# PG4_SHEET2.net
KiCad netlist of a schematic drawn in Altium Designer
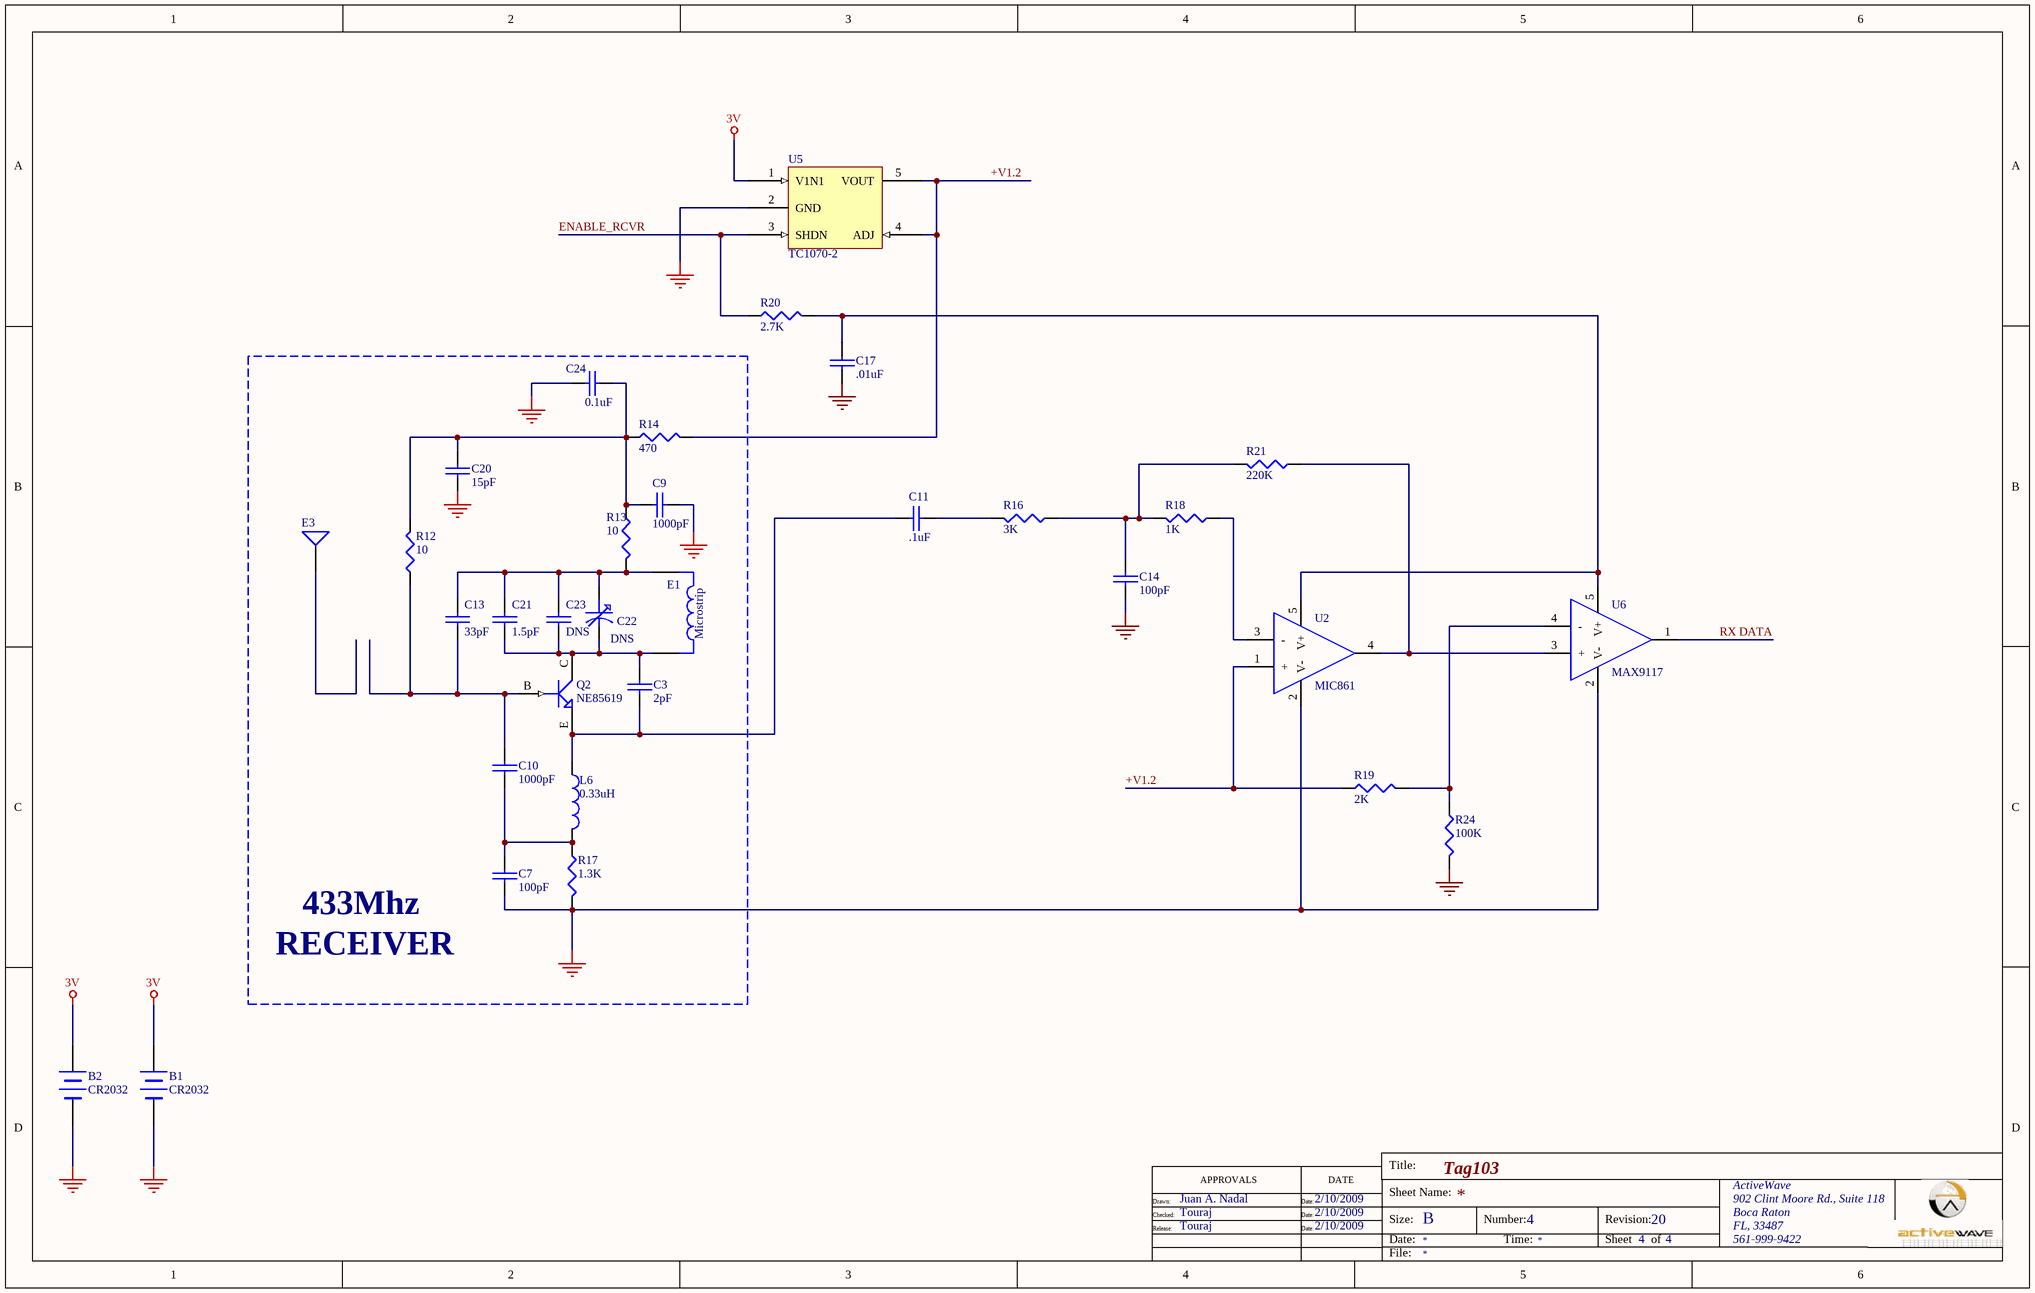
[diagram p0: PG4 SHEET2.schdoc]

(export (version "E")
  (design (tool "Eeschema 10.0.6"))
  (components
    (comp (ref "B1")
      (value "CR2032")
      (footprint "BATT HOLDER1")
      (description "Battery")
      (fields (field (name "Comment") "BATT HOLDER COIN CR2032 CUT"))
      (libsource (lib "ActiveWave MasterLib") (part "BATTERY2"))
    )
    (comp (ref "B2")
      (value "CR2032")
      (footprint "BATT HOLDER COIN CR2032 CUT_VER1")
      (description "Battery")
      (fields (field (name "Comment") "BATT HOLDER COIN CR2032 CUT"))
      (libsource (lib "ActiveWave MasterLib") (part "BATTERY2"))
    )
    (comp (ref "C3")
      (value "2pF")
      (footprint "0603")
      (description "Capacitor")
      (fields (field (name "Comment") "2 pF"))
      (libsource (lib "ActiveWave MasterLib") (part "CAP-0603"))
    )
    (comp (ref "C7")
      (value "100pF")
      (footprint "0603")
      (description "Capacitor")
      (fields (field (name "Comment") "100 pF"))
      (libsource (lib "ActiveWave MasterLib") (part "CAP-0603"))
    )
    (comp (ref "C9")
      (value "1000pF")
      (footprint "0603")
      (description "Capacitor")
      (fields (field (name "Comment") "1000 pF"))
      (libsource (lib "ActiveWave MasterLib") (part "CAP-0603"))
    )
    (comp (ref "C10")
      (value "1000pF")
      (footprint "0603")
      (description "Capacitor")
      (fields (field (name "Comment") "1000 pF"))
      (libsource (lib "ActiveWave MasterLib") (part "CAP-0603"))
    )
    (comp (ref "C11")
      (value ".1uF")
      (footprint "0603")
      (description "Capacitor")
      (libsource (lib "ActiveWave MasterLib") (part "CAP-0603"))
    )
    (comp (ref "C13")
      (value "33pF")
      (footprint "0603")
      (description "Capacitor")
      (fields (field (name "Comment") "33 pF"))
      (libsource (lib "ActiveWave MasterLib") (part "CAP-0603"))
    )
    (comp (ref "C14")
      (value "100pF")
      (footprint "0603")
      (description "Capacitor")
      (libsource (lib "ActiveWave MasterLib") (part "CAP-0603"))
    )
    (comp (ref "C17")
      (value ".01uF")
      (footprint "0603")
      (description "Capacitor")
      (libsource (lib "ActiveWave MasterLib") (part "CAP-0603"))
    )
    (comp (ref "C20")
      (value "15pF")
      (footprint "0603")
      (description "Capacitor")
      (libsource (lib "ActiveWave MasterLib") (part "CAP-0603"))
    )
    (comp (ref "C21")
      (value "1.5pF")
      (footprint "0603")
      (description "Capacitor")
      (libsource (lib "ActiveWave MasterLib") (part "CAP-0603"))
    )
    (comp (ref "C22") (value "DNS") (footprint "0603") (libsource (lib "*") (part "CAPACITOR VAR")))
    (comp (ref "C23")
      (value "DNS")
      (footprint "0603")
      (description "Capacitor")
      (libsource (lib "ActiveWave MasterLib") (part "CAP-0603"))
    )
    (comp (ref "C24")
      (value "0.1uF")
      (footprint "0603")
      (description "Capacitor")
      (fields (field (name "Comment") "0.1 uF"))
      (libsource (lib "ActiveWave MasterLib") (part "CAP-0603"))
    )
    (comp (ref "E1")
      (value "Microstrip")
      (footprint "Antenna")
      (fields (field (name "ITEM-DESCRIPTION") "Microstrip"))
      (libsource (lib "ActiveWave MasterLib") (part "ANTENNA"))
    )
    (comp (ref "E3")
      (value "*")
      (footprint "Antenna1")
      (libsource (lib "ActiveWave MasterLib") (part "Antenna1"))
    )
    (comp (ref "L6")
      (value "0.33uH")
      (footprint "0603")
      (libsource (lib "ActiveWave MasterLib") (part "INDUCTOR"))
    )
    (comp (ref "Q2")
      (value "NE85619")
      (footprint "3 PIN ULTRA SUPER MINI MOLD")
      (description "NPN Transistor")
      (libsource (lib "ActiveWave MasterLib") (part "NE85619"))
    )
    (comp (ref "R12")
      (value "10")
      (footprint "0603")
      (libsource (lib "ActiveWave MasterLib") (part "RES-0603"))
    )
    (comp (ref "R13")
      (value "10")
      (footprint "0603")
      (libsource (lib "ActiveWave MasterLib") (part "RES-0603"))
    )
    (comp (ref "R14")
      (value "470")
      (footprint "0603")
      (libsource (lib "ActiveWave MasterLib") (part "RES-0603"))
    )
    (comp (ref "R16")
      (value "3K")
      (footprint "0603")
      (fields (field (name "Comment") "22K"))
      (libsource (lib "ActiveWave MasterLib") (part "RES-0603"))
    )
    (comp (ref "R17")
      (value "1.3K")
      (footprint "0603")
      (fields (field (name "Comment") "2K"))
      (libsource (lib "ActiveWave MasterLib") (part "RES-0603"))
    )
    (comp (ref "R18")
      (value "1K")
      (footprint "0603")
      (libsource (lib "ActiveWave MasterLib") (part "RES-0603"))
    )
    (comp (ref "R19")
      (value "2K")
      (footprint "0603")
      (libsource (lib "ActiveWave MasterLib") (part "RES-0603"))
    )
    (comp (ref "R20")
      (value "2.7K")
      (footprint "0603")
      (libsource (lib "ActiveWave MasterLib") (part "RES-0603"))
    )
    (comp (ref "R21")
      (value "220K")
      (footprint "0603")
      (libsource (lib "ActiveWave MasterLib") (part "RES-0603"))
    )
    (comp (ref "R24")
      (value "100K")
      (footprint "0603")
      (libsource (lib "ActiveWave MasterLib") (part "RES-0603"))
    )
    (comp (ref "U2")
      (value "MIC861")
      (footprint "SC70")
      (libsource (lib "ActiveWave MasterLib") (part "OPAMP MIC861"))
    )
    (comp (ref "U5")
      (value "TC1070-2")
      (footprint "SOT23-5A")
      (fields (field (name "Comment") "TC1070"))
      (libsource (lib "ActiveWave MasterLib") (part "TC1070-2"))
    )
    (comp (ref "U6")
      (value "MAX9117")
      (footprint "SC70")
      (fields (field (name "Comment") "MAX9119EXK+"))
      (libsource (lib "ActiveWave MasterLib") (part "COMPARATOR MAX9117"))
    )
  )
  (nets
    (net (code "1") (name "/+V1.2") (class "Default")
      (node (ref "R14") (pin "2") (pinfunction "2_2") (pintype "passive"))
      (node (ref "R19") (pin "1") (pinfunction "1_1") (pintype "passive"))
      (node (ref "U2") (pin "1") (pinfunction "+_1") (pintype "passive"))
      (node (ref "U5") (pin "4") (pinfunction "ADJ_4") (pintype "input"))
      (node (ref "U5") (pin "5") (pinfunction "VOUT_5") (pintype "power_in"))
    )
    (net (code "2") (name "/ENABLE_RCVR") (class "Default")
      (node (ref "R20") (pin "1") (pinfunction "1_1") (pintype "passive"))
      (node (ref "U5") (pin "3") (pinfunction "SHDN_3") (pintype "input"))
    )
    (net (code "3") (name "/RX DATA") (class "Default")
      (node (ref "U6") (pin "1") (pinfunction "OUT_1") (pintype "passive"))
    )
    (net (code "4") (name "3V") (class "Default")
      (node (ref "B1") (pin "2") (pinfunction "+_2") (pintype "passive"))
      (node (ref "B2") (pin "2") (pinfunction "+_2") (pintype "passive"))
      (node (ref "U5") (pin "1") (pinfunction "V1N1_1") (pintype "input"))
    )
    (net (code "5") (name "GND") (class "Default")
      (node (ref "B1") (pin "1") (pinfunction "-_1") (pintype "passive"))
      (node (ref "B2") (pin "1") (pinfunction "-_1") (pintype "passive"))
      (node (ref "C14") (pin "1") (pinfunction "1_1") (pintype "passive"))
      (node (ref "C17") (pin "2") (pinfunction "2_2") (pintype "passive"))
      (node (ref "C20") (pin "2") (pinfunction "2_2") (pintype "passive"))
      (node (ref "C24") (pin "2") (pinfunction "2_2") (pintype "passive"))
      (node (ref "C7") (pin "2") (pinfunction "2_2") (pintype "passive"))
      (node (ref "C9") (pin "2") (pinfunction "2_2") (pintype "passive"))
      (node (ref "R17") (pin "2") (pinfunction "2_2") (pintype "passive"))
      (node (ref "R24") (pin "2") (pinfunction "2_2") (pintype "passive"))
      (node (ref "U2") (pin "2") (pinfunction "V-_2") (pintype "passive"))
      (node (ref "U5") (pin "2") (pinfunction "GND_2") (pintype "power_in"))
      (node (ref "U6") (pin "2") (pinfunction "V-_2") (pintype "passive"))
    )
    (net (code "6") (name "Net-(C10-Pad1)") (class "Default")
      (node (ref "C10") (pin "1") (pinfunction "1_1") (pintype "passive"))
      (node (ref "C13") (pin "2") (pinfunction "2_2") (pintype "passive"))
      (node (ref "Q2") (pin "B") (pinfunction "B_B") (pintype "input"))
      (node (ref "R12") (pin "1") (pinfunction "1_1") (pintype "passive"))
    )
    (net (code "7") (name "Net-(C10-Pad2)") (class "Default")
      (node (ref "C10") (pin "2") (pinfunction "2_2") (pintype "passive"))
      (node (ref "C7") (pin "1") (pinfunction "1_1") (pintype "passive"))
      (node (ref "L6") (pin "2") (pinfunction "2_2") (pintype "passive"))
      (node (ref "R17") (pin "1") (pinfunction "1_1") (pintype "passive"))
    )
    (net (code "8") (name "Net-(C11-Pad1)") (class "Default")
      (node (ref "C11") (pin "1") (pinfunction "1_1") (pintype "passive"))
      (node (ref "C3") (pin "2") (pinfunction "2_2") (pintype "passive"))
      (node (ref "L6") (pin "1") (pinfunction "1_1") (pintype "passive"))
      (node (ref "Q2") (pin "E") (pinfunction "E_E") (pintype "passive"))
    )
    (net (code "9") (name "Net-(C11-Pad2)") (class "Default")
      (node (ref "C11") (pin "2") (pinfunction "2_2") (pintype "passive"))
      (node (ref "R16") (pin "2") (pinfunction "2_2") (pintype "passive"))
    )
    (net (code "10") (name "Net-(C13-Pad1)") (class "Default")
      (node (ref "C13") (pin "1") (pinfunction "1_1") (pintype "passive"))
      (node (ref "C21") (pin "1") (pinfunction "1_1") (pintype "passive"))
      (node (ref "C22") (pin "1") (pinfunction "1_1") (pintype "passive"))
      (node (ref "C23") (pin "1") (pinfunction "1_1") (pintype "passive"))
      (node (ref "E1") (pin "1") (pinfunction "1_1") (pintype "passive"))
      (node (ref "R13") (pin "2") (pinfunction "2_2") (pintype "passive"))
    )
    (net (code "11") (name "Net-(C14-Pad2)") (class "Default")
      (node (ref "C14") (pin "2") (pinfunction "2_2") (pintype "passive"))
      (node (ref "R16") (pin "1") (pinfunction "1_1") (pintype "passive"))
      (node (ref "R18") (pin "2") (pinfunction "2_2") (pintype "passive"))
      (node (ref "R21") (pin "2") (pinfunction "2_2") (pintype "passive"))
    )
    (net (code "12") (name "Net-(C20-Pad1)") (class "Default")
      (node (ref "C20") (pin "1") (pinfunction "1_1") (pintype "passive"))
      (node (ref "C24") (pin "1") (pinfunction "1_1") (pintype "passive"))
      (node (ref "C9") (pin "1") (pinfunction "1_1") (pintype "passive"))
      (node (ref "R12") (pin "2") (pinfunction "2_2") (pintype "passive"))
      (node (ref "R13") (pin "1") (pinfunction "1_1") (pintype "passive"))
      (node (ref "R14") (pin "1") (pinfunction "1_1") (pintype "passive"))
    )
    (net (code "13") (name "Net-(C21-Pad2)") (class "Default")
      (node (ref "C21") (pin "2") (pinfunction "2_2") (pintype "passive"))
      (node (ref "C22") (pin "2") (pinfunction "2_2") (pintype "passive"))
      (node (ref "C23") (pin "2") (pinfunction "2_2") (pintype "passive"))
      (node (ref "C3") (pin "1") (pinfunction "1_1") (pintype "passive"))
      (node (ref "E1") (pin "2") (pinfunction "2_2") (pintype "passive"))
      (node (ref "Q2") (pin "C") (pinfunction "C_C") (pintype "passive"))
    )
    (net (code "14") (name "Net-(U2--)") (class "Default")
      (node (ref "R18") (pin "1") (pinfunction "1_1") (pintype "passive"))
      (node (ref "U2") (pin "3") (pinfunction "-_3") (pintype "passive"))
    )
    (net (code "15") (name "Net-(U2-OUT)") (class "Default")
      (node (ref "R21") (pin "1") (pinfunction "1_1") (pintype "passive"))
      (node (ref "U2") (pin "4") (pinfunction "OUT_4") (pintype "passive"))
      (node (ref "U6") (pin "3") (pinfunction "+_3") (pintype "passive"))
    )
    (net (code "16") (name "Net-(U2-V+)") (class "Default")
      (node (ref "C17") (pin "1") (pinfunction "1_1") (pintype "passive"))
      (node (ref "R20") (pin "2") (pinfunction "2_2") (pintype "passive"))
      (node (ref "U2") (pin "5") (pinfunction "V+_5") (pintype "passive"))
      (node (ref "U6") (pin "5") (pinfunction "V+_5") (pintype "passive"))
    )
    (net (code "17") (name "Net-(U6--)") (class "Default")
      (node (ref "R19") (pin "2") (pinfunction "2_2") (pintype "passive"))
      (node (ref "R24") (pin "1") (pinfunction "1_1") (pintype "passive"))
      (node (ref "U6") (pin "4") (pinfunction "-_4") (pintype "passive"))
    )
    (net (code "18") (name "unconnected-(E3-Pad1)") (class "Default")
      (node (ref "E3") (pin "1") (pinfunction "1_1") (pintype "passive"))
    )
  )
)
